# Sheet1.net
KiCad netlist of a schematic drawn in Altium Designer
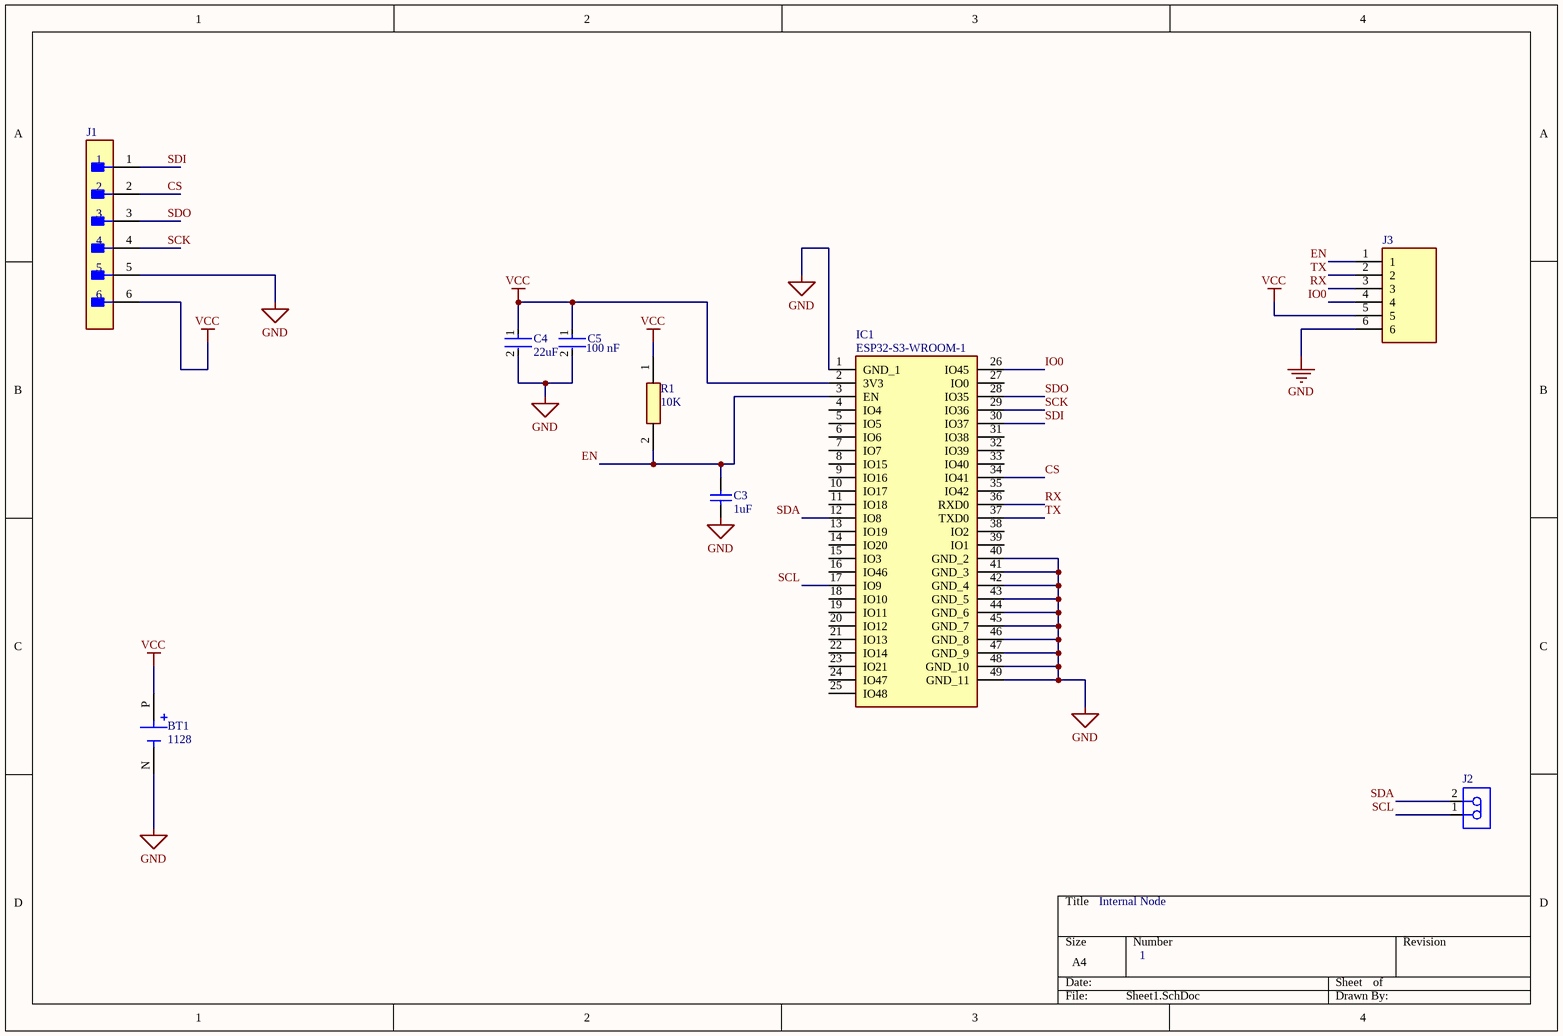
[diagram p0: Sheet1.SchDoc]

(export (version "E")
  (design (tool "Eeschema 10.0.6"))
  (components
    (comp (ref "BT1")
      (value "1128")
      (footprint "BAT_1128")
      (description "SMT Holder for CR123A Battery w/ coil spring")
      (fields (field (name "MF") "Keystone Electronics"))
      (libsource (lib "1128") (part "1128"))
    )
    (comp (ref "C3")
      (value "1uF")
      (footprint "CAPC2013X140X50LL20T25")
      (fields
        (field (name "PART NUMBER") "0805ZC105KAZ2A")
        (field (name "MANUFACTURER") "AVX Interconnect / Elco")
      )
      (libsource (lib "Altium Content Vault") (part "CAP"))
    )
    (comp (ref "C4")
      (value "22uF")
      (footprint "FP-CL21-IPC_C")
      (description "CL21 Series 0805 22uF 16V ±20% Tolerance X5R Multilayer Ceramic Chip Capacitor")
      (fields (field (name "TOLERANCE") "20%"))
      (libsource (lib "Altium Content Vault") (part "b4654b650e69147ec39a6b967a45e02"))
    )
    (comp (ref "C5")
      (value "CC0805KRX7R7BB104")
      (footprint "FP-CC0805-0_85-MFG")
      (description "CAP CER 0.1UF 16V X7R 0805")
      (fields
        (field (name "MANUFACTURER") "Yageo")
        (field (name "OCTOPART") "https://octopart.com/cc0805krx7r7bb104-yageo-39467769")
        (field (name "CAPACITANCE") "100 nF")
      )
      (libsource (lib "Altium Content Vault") (part "11868f565c42a9108669ba33697ecf6"))
    )
    (comp (ref "IC1")
      (value "ESP32-S3-WROOM-1")
      (footprint "SamacSys:ESP32S3WROOM1")
      (description "Integrated Circuit")
      (libsource (lib "*") (part "ESP32-S3-WROOM-1"))
    )
    (comp (ref "J1")
      (value "B6B-PH-K-K(LF)(SN)")
      (footprint "FP-B6B-PH-K-K_LF_SN-MFG")
      (description "PH Series 6 Position 2 mm Pitch Through Hole Top Entry Shrouded Header")
      (libsource (lib "Altium Content Vault") (part "f2cb566baf1c37ab5a3b8e90bbeafd6"))
    )
    (comp (ref "J2")
      (value "B2B-PH-K-S(LF)(SN)")
      (footprint "JST-B2B-PH-K-S_V")
      (fields (field (name "MANUFACTURER") "JST"))
      (libsource (lib "Altium Content Vault") (part "CN-2P-F-QF2"))
    )
    (comp (ref "J3")
      (value "22-28-4060")
      (footprint "SamacSys:HDRV6W66P0X254_1X6_1524X249X838P")
      (description "Connector")
      (fields (field (name "MOUSER PART NUMBER") "538-22-28-4060"))
      (libsource (lib "*") (part "22-28-4060"))
    )
    (comp (ref "R1")
      (value "10K")
      (footprint "SamacSys:RESC2012X60N")
      (description "Resistor")
      (fields
        (field (name "MANUFACTURER_PART_NUMBER") "CMP0805AFX-1002ELF")
        (field (name "MOUSER PART NUMBER") "652-CMP0805AFX-1002L")
      )
      (libsource (lib "*") (part "CMP0805AFX-1002ELF"))
    )
  )
  (nets
    (net (code "1") (name "/CS") (class "Default")
      (node (ref "IC1") (pin "34") (pinfunction "IO41_34") (pintype "passive"))
      (node (ref "J1") (pin "2") (pinfunction "2_2") (pintype "passive"))
    )
    (net (code "2") (name "/EN") (class "Default")
      (node (ref "C3") (pin "2") (pinfunction "2_2") (pintype "passive"))
      (node (ref "IC1") (pin "3") (pinfunction "EN_3") (pintype "passive"))
      (node (ref "J3") (pin "1") (pinfunction "1_1") (pintype "passive"))
      (node (ref "R1") (pin "2") (pinfunction "2_2") (pintype "passive"))
    )
    (net (code "3") (name "/IO0") (class "Default")
      (node (ref "IC1") (pin "26") (pinfunction "IO45_26") (pintype "passive"))
      (node (ref "J3") (pin "4") (pinfunction "4_4") (pintype "passive"))
    )
    (net (code "4") (name "/RX") (class "Default")
      (node (ref "IC1") (pin "36") (pinfunction "RXD0_36") (pintype "passive"))
      (node (ref "J3") (pin "3") (pinfunction "3_3") (pintype "passive"))
    )
    (net (code "5") (name "/SCK") (class "Default")
      (node (ref "IC1") (pin "29") (pinfunction "IO36_29") (pintype "passive"))
      (node (ref "J1") (pin "4") (pinfunction "4_4") (pintype "passive"))
    )
    (net (code "6") (name "/SCL") (class "Default")
      (node (ref "IC1") (pin "17") (pinfunction "IO9_17") (pintype "passive"))
      (node (ref "J2") (pin "1") (pinfunction "1_1") (pintype "passive"))
    )
    (net (code "7") (name "/SDA") (class "Default")
      (node (ref "IC1") (pin "12") (pinfunction "IO8_12") (pintype "passive"))
      (node (ref "J2") (pin "2") (pinfunction "2_2") (pintype "passive"))
    )
    (net (code "8") (name "/SDI") (class "Default")
      (node (ref "IC1") (pin "30") (pinfunction "IO37_30") (pintype "passive"))
      (node (ref "J1") (pin "1") (pinfunction "1_1") (pintype "passive"))
    )
    (net (code "9") (name "/SDO") (class "Default")
      (node (ref "IC1") (pin "28") (pinfunction "IO35_28") (pintype "passive"))
      (node (ref "J1") (pin "3") (pinfunction "3_3") (pintype "passive"))
    )
    (net (code "10") (name "/TX") (class "Default")
      (node (ref "IC1") (pin "37") (pinfunction "TXD0_37") (pintype "passive"))
      (node (ref "J3") (pin "2") (pinfunction "2_2") (pintype "passive"))
    )
    (net (code "11") (name "GND") (class "Default")
      (node (ref "BT1") (pin "N") (pinfunction "NEG_N") (pintype "passive"))
      (node (ref "C3") (pin "1") (pinfunction "1_1") (pintype "passive"))
      (node (ref "C4") (pin "2") (pinfunction "2_2") (pintype "passive"))
      (node (ref "C5") (pin "2") (pinfunction "2_2") (pintype "passive"))
      (node (ref "IC1") (pin "1") (pinfunction "GND_1_1") (pintype "passive"))
      (node (ref "IC1") (pin "40") (pinfunction "GND_2_40") (pintype "passive"))
      (node (ref "IC1") (pin "41") (pinfunction "GND_3_41") (pintype "passive"))
      (node (ref "IC1") (pin "42") (pinfunction "GND_4_42") (pintype "passive"))
      (node (ref "IC1") (pin "43") (pinfunction "GND_5_43") (pintype "passive"))
      (node (ref "IC1") (pin "44") (pinfunction "GND_6_44") (pintype "passive"))
      (node (ref "IC1") (pin "45") (pinfunction "GND_7_45") (pintype "passive"))
      (node (ref "IC1") (pin "46") (pinfunction "GND_8_46") (pintype "passive"))
      (node (ref "IC1") (pin "47") (pinfunction "GND_9_47") (pintype "passive"))
      (node (ref "IC1") (pin "48") (pinfunction "GND_10_48") (pintype "passive"))
      (node (ref "IC1") (pin "49") (pinfunction "GND_11_49") (pintype "passive"))
      (node (ref "J1") (pin "5") (pinfunction "5_5") (pintype "passive"))
      (node (ref "J3") (pin "6") (pinfunction "6_6") (pintype "passive"))
    )
    (net (code "12") (name "VCC") (class "Default")
      (node (ref "BT1") (pin "P") (pinfunction "POS_P") (pintype "passive"))
      (node (ref "C4") (pin "1") (pinfunction "1_1") (pintype "passive"))
      (node (ref "C5") (pin "1") (pinfunction "1_1") (pintype "passive"))
      (node (ref "IC1") (pin "2") (pinfunction "3V3_2") (pintype "passive"))
      (node (ref "J1") (pin "6") (pinfunction "6_6") (pintype "passive"))
      (node (ref "J3") (pin "5") (pinfunction "5_5") (pintype "passive"))
      (node (ref "R1") (pin "1") (pinfunction "1_1") (pintype "passive"))
    )
    (net (code "13") (name "unconnected-(IC1-IO0-Pad27)") (class "Default")
      (node (ref "IC1") (pin "27") (pinfunction "IO0_27") (pintype "passive"))
    )
    (net (code "14") (name "unconnected-(IC1-IO1-Pad39)") (class "Default")
      (node (ref "IC1") (pin "39") (pinfunction "IO1_39") (pintype "passive"))
    )
    (net (code "15") (name "unconnected-(IC1-IO2-Pad38)") (class "Default")
      (node (ref "IC1") (pin "38") (pinfunction "IO2_38") (pintype "passive"))
    )
    (net (code "16") (name "unconnected-(IC1-IO3-Pad15)") (class "Default")
      (node (ref "IC1") (pin "15") (pinfunction "IO3_15") (pintype "passive"))
    )
    (net (code "17") (name "unconnected-(IC1-IO4-Pad4)") (class "Default")
      (node (ref "IC1") (pin "4") (pinfunction "IO4_4") (pintype "passive"))
    )
    (net (code "18") (name "unconnected-(IC1-IO5-Pad5)") (class "Default")
      (node (ref "IC1") (pin "5") (pinfunction "IO5_5") (pintype "passive"))
    )
    (net (code "19") (name "unconnected-(IC1-IO6-Pad6)") (class "Default")
      (node (ref "IC1") (pin "6") (pinfunction "IO6_6") (pintype "passive"))
    )
    (net (code "20") (name "unconnected-(IC1-IO7-Pad7)") (class "Default")
      (node (ref "IC1") (pin "7") (pinfunction "IO7_7") (pintype "passive"))
    )
    (net (code "21") (name "unconnected-(IC1-IO10-Pad18)") (class "Default")
      (node (ref "IC1") (pin "18") (pinfunction "IO10_18") (pintype "passive"))
    )
    (net (code "22") (name "unconnected-(IC1-IO11-Pad19)") (class "Default")
      (node (ref "IC1") (pin "19") (pinfunction "IO11_19") (pintype "passive"))
    )
    (net (code "23") (name "unconnected-(IC1-IO12-Pad20)") (class "Default")
      (node (ref "IC1") (pin "20") (pinfunction "IO12_20") (pintype "passive"))
    )
    (net (code "24") (name "unconnected-(IC1-IO13-Pad21)") (class "Default")
      (node (ref "IC1") (pin "21") (pinfunction "IO13_21") (pintype "passive"))
    )
    (net (code "25") (name "unconnected-(IC1-IO14-Pad22)") (class "Default")
      (node (ref "IC1") (pin "22") (pinfunction "IO14_22") (pintype "passive"))
    )
    (net (code "26") (name "unconnected-(IC1-IO15-Pad8)") (class "Default")
      (node (ref "IC1") (pin "8") (pinfunction "IO15_8") (pintype "passive"))
    )
    (net (code "27") (name "unconnected-(IC1-IO16-Pad9)") (class "Default")
      (node (ref "IC1") (pin "9") (pinfunction "IO16_9") (pintype "passive"))
    )
    (net (code "28") (name "unconnected-(IC1-IO17-Pad10)") (class "Default")
      (node (ref "IC1") (pin "10") (pinfunction "IO17_10") (pintype "passive"))
    )
    (net (code "29") (name "unconnected-(IC1-IO18-Pad11)") (class "Default")
      (node (ref "IC1") (pin "11") (pinfunction "IO18_11") (pintype "passive"))
    )
    (net (code "30") (name "unconnected-(IC1-IO19-Pad13)") (class "Default")
      (node (ref "IC1") (pin "13") (pinfunction "IO19_13") (pintype "passive"))
    )
    (net (code "31") (name "unconnected-(IC1-IO20-Pad14)") (class "Default")
      (node (ref "IC1") (pin "14") (pinfunction "IO20_14") (pintype "passive"))
    )
    (net (code "32") (name "unconnected-(IC1-IO21-Pad23)") (class "Default")
      (node (ref "IC1") (pin "23") (pinfunction "IO21_23") (pintype "passive"))
    )
    (net (code "33") (name "unconnected-(IC1-IO38-Pad31)") (class "Default")
      (node (ref "IC1") (pin "31") (pinfunction "IO38_31") (pintype "passive"))
    )
    (net (code "34") (name "unconnected-(IC1-IO39-Pad32)") (class "Default")
      (node (ref "IC1") (pin "32") (pinfunction "IO39_32") (pintype "passive"))
    )
    (net (code "35") (name "unconnected-(IC1-IO40-Pad33)") (class "Default")
      (node (ref "IC1") (pin "33") (pinfunction "IO40_33") (pintype "passive"))
    )
    (net (code "36") (name "unconnected-(IC1-IO42-Pad35)") (class "Default")
      (node (ref "IC1") (pin "35") (pinfunction "IO42_35") (pintype "passive"))
    )
    (net (code "37") (name "unconnected-(IC1-IO46-Pad16)") (class "Default")
      (node (ref "IC1") (pin "16") (pinfunction "IO46_16") (pintype "passive"))
    )
    (net (code "38") (name "unconnected-(IC1-IO47-Pad24)") (class "Default")
      (node (ref "IC1") (pin "24") (pinfunction "IO47_24") (pintype "passive"))
    )
    (net (code "39") (name "unconnected-(IC1-IO48-Pad25)") (class "Default")
      (node (ref "IC1") (pin "25") (pinfunction "IO48_25") (pintype "passive"))
    )
  )
)
